# PSU.net
KiCad netlist of a schematic drawn in Altium Designer
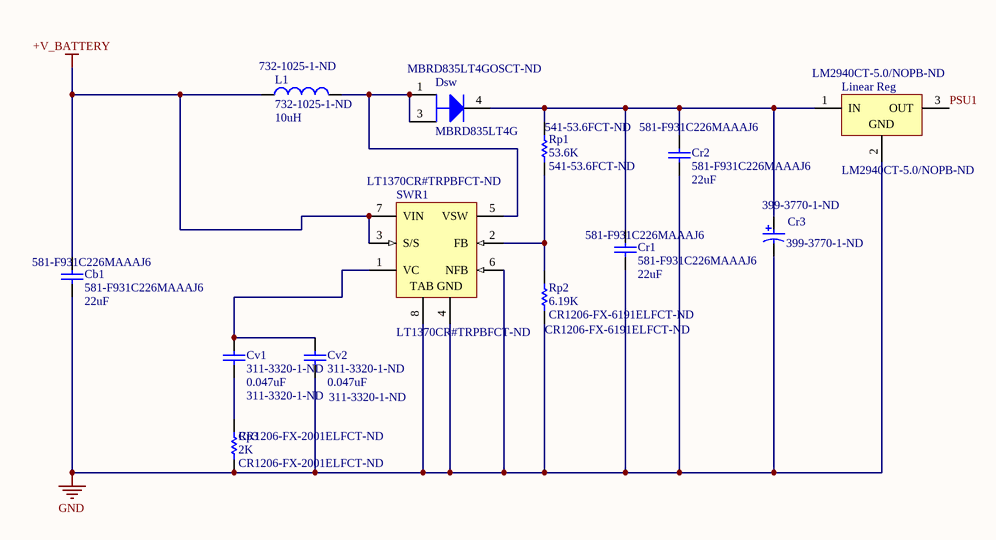
[diagram p0: PSU.SchDoc]

(export (version "E")
  (design (tool "Eeschema 10.0.6"))
  (components
    (comp (ref "Cb1")
      (value "581-F931C226MAAAJ6")
      (footprint "C1206")
      (fields
        (field (name "ALTIUM_VALUE") "22uF")
        (field (name "SUPPLIER PART NUMBER 1") "581-F931C226MAAAJ6")
        (field (name "MANUFACTURER") "Kyocera AVX")
        (field (name "MANUFACTURER PART NUMBER") "F931C226MAAAJ6")
        (field (name "PUBLISHER") "Altium Limited")
      )
      (libsource (lib "Miscellaneous Devices") (part "Cap"))
    )
    (comp (ref "Cr1")
      (value "581-F931C226MAAAJ6")
      (footprint "C1206")
      (fields
        (field (name "ALTIUM_VALUE") "22uF")
        (field (name "SUPPLIER PART NUMBER 1") "581-F931C226MAAAJ6")
        (field (name "MANUFACTURER") "Kyocera AVX")
        (field (name "MANUFACTURER PART NUMBER") "F931C226MAAAJ6")
        (field (name "PUBLISHER") "Altium Limited")
      )
      (libsource (lib "Miscellaneous Devices") (part "Cap"))
    )
    (comp (ref "Cr2")
      (value "581-F931C226MAAAJ6")
      (footprint "C1206")
      (fields
        (field (name "ALTIUM_VALUE") "22uF")
        (field (name "SUPPLIER PART NUMBER 1") "581-F931C226MAAAJ6")
        (field (name "MANUFACTURER") "Kyocera AVX")
        (field (name "MANUFACTURER PART NUMBER") "F931C226MAAAJ6")
        (field (name "PUBLISHER") "Altium Limited")
      )
      (libsource (lib "Miscellaneous Devices") (part "Cap"))
    )
    (comp (ref "Cr3")
      (value "399-3770-1-ND")
      (footprint "KEMT-T491-D_L")
      (fields
        (field (name "MANUFACTURER") "Kemet")
        (field (name "VOLTAGE") "16V")
        (field (name "TOLERANCE") "10%")
        (field (name "SUPPLIER PART NUMBER 1") "399-3770-1-ND")
      )
      (libsource (lib "Altium Content Vault") (part "CAP-P-2"))
    )
    (comp (ref "Cv1")
      (value "311-3320-1-ND")
      (footprint "C1206")
      (description "CAP CER 0.47UF 4V X5R 0201, Digi-key")
      (fields
        (field (name "ALTIUM_VALUE") "0.047uF")
        (field (name "SUPPLIER PART NUMBER 1") "311-3320-1-ND")
        (field (name "MANUFACTURER") "Yageo")
        (field (name "MANUFACTURER PART NUMBER") "CC0201MRX5R4BB474")
        (field (name "PUBLISHER") "Altium Limited")
      )
      (libsource (lib "Miscellaneous Devices") (part "Cap"))
    )
    (comp (ref "Cv2")
      (value "311-3320-1-ND")
      (footprint "C1206")
      (description "CAP CER 0.47UF 4V X5R 0201, Digi-key")
      (fields
        (field (name "ALTIUM_VALUE") "0.047uF")
        (field (name "SUPPLIER PART NUMBER 1") "311-3320-1-ND")
        (field (name "MANUFACTURER") "Yageo")
        (field (name "MANUFACTURER PART NUMBER") "CC0201MRX5R4BB474")
        (field (name "PUBLISHER") "Altium Limited")
      )
      (libsource (lib "Miscellaneous Devices") (part "Cap"))
    )
    (comp (ref "Dsw")
      (value "MBRD835LT4G")
      (footprint "ONSC-DPAK-3-369C-01_V")
      (description "SWITCHMODE(TM) Power Rectifier, 3-Pin DPAK, Pb-Free, Tape and Reel, Digi-key")
      (fields
        (field (name "MANUFACTURER") "On Semiconductor")
        (field (name "SUPPLIER PART NUMBER 1") "MBRD835LT4GOSCT-ND")
      )
      (libsource (lib "Altium Content Vault") (part "ONSC-D-A1A3K4-3_A"))
    )
    (comp (ref "L1")
      (value "732-1025-1-ND")
      (footprint "2029")
      (description "Inductor, SMD 10 uH 1.3 A ±30%, 744042100, Würth Elektronik, Digi-key")
      (fields
        (field (name "ALTIUM_VALUE") "10uH")
        (field (name "SUPPLIER PART NUMBER 1") "732-1025-1-ND")
        (field (name "MANUFACTURER") "Wurth Electronics")
        (field (name "MANUFACTURER PART NUMBER") "744042100")
        (field (name "PUBLISHER") "Altium Limited")
      )
      (libsource (lib "Miscellaneous Devices") (part "Inductor"))
    )
    (comp (ref "Linear Reg")
      (value "LM2940CT-5.0/NOPB-ND")
      (footprint "NDE0003A")
      (description "1A Low Dropout Regulator, 3-pin TO-220, Pb-Free, Digi-key")
      (fields
        (field (name "MANUFACTURER") "Texas Instruments")
        (field (name "SUPPLIER PART NUMBER 1") "LM2940CT-5.0/NOPB-ND")
      )
      (libsource (lib "Altium Content Vault") (part "PM-REG-LM2940-SIL3"))
    )
    (comp (ref "Rp1")
      (value "541-53.6FCT-ND")
      (footprint "C1206")
      (description "Res Thick Film 1206 53.6 Ohm 1% 0.25W(1/4W) ±100ppm/C Molded SMD Automotive Paper T/R, Digi-key")
      (fields
        (field (name "ALTIUM_VALUE") "53.6K")
        (field (name "SUPPLIER PART NUMBER 1") "541-53.6FCT-ND")
        (field (name "MANUFACTURER") "Vishay")
        (field (name "MANUFACTURER PART NUMBER") "CRCW120653R6FKEA")
        (field (name "PUBLISHER") "Altium Limited")
      )
      (libsource (lib "Miscellaneous Devices") (part "Res1"))
    )
    (comp (ref "Rp2")
      (value "CR1206-FX-6191ELFCT-ND")
      (footprint "C1206")
      (description "Thick Film Resistors 6.19K 1%,Digi-key")
      (fields
        (field (name "ALTIUM_VALUE") "6.19K")
        (field (name "SUPPLIER PART NUMBER 1") "CR1206-FX-6191ELFCT-ND")
        (field (name "MANUFACTURER") "Bourns")
        (field (name "MANUFACTURER PART NUMBER") "CR1206-FX-6191ELF")
        (field (name "PUBLISHER") "Altium Limited")
      )
      (libsource (lib "Miscellaneous Devices") (part "Res1"))
    )
    (comp (ref "Rp3")
      (value "CR1206-FX-2001ELFCT-ND")
      (footprint "C1206")
      (description "BOURNS - CR1206-FX-2001ELF - RES, 2K, 1%, 0.25W, 1206, THICK FILM, Digi-key")
      (fields
        (field (name "ALTIUM_VALUE") "2K")
        (field (name "SUPPLIER PART NUMBER 1") "CR1206-FX-2001ELFCT-ND")
        (field (name "MANUFACTURER") "Bourns")
        (field (name "MANUFACTURER PART NUMBER") "CR1206-FX-2001ELF")
        (field (name "PUBLISHER") "Altium Limited")
      )
      (libsource (lib "Miscellaneous Devices") (part "Res1"))
    )
    (comp (ref "SWR1")
      (value "LT1370CR#TRPBFCT-ND")
      (footprint "LT-R-7_L")
      (description "500 kHz High Efficiency 6 A Switching Regulator, 7-pin DPAK (R-7), 0 to 125 degC, Digi-key")
      (fields
        (field (name "MANUFACTURER") "Linear Technology")
        (field (name "PARTNUMBER") "LT1370CR")
        (field (name "SUPPLIER PART NUMBER 1") "LT1370CR#TRPBFCT-ND")
      )
      (libsource (lib "Altium Content Vault") (part "LT-LT1370X-R-7"))
    )
  )
  (nets
    (net (code "1") (name "+V_BATTERY") (class "Default")
      (node (ref "Cb1") (pin "2") (pinfunction "2_2") (pintype "passive"))
      (node (ref "L1") (pin "1") (pinfunction "1_1") (pintype "passive"))
      (node (ref "SWR1") (pin "3") (pinfunction "S/S_3") (pintype "input"))
      (node (ref "SWR1") (pin "7") (pinfunction "VIN_7") (pintype "power_in"))
    )
    (net (code "2") (name "/PSU1") (class "Default")
      (node (ref "Linear Reg") (pin "3") (pinfunction "OUT_3") (pintype "power_in"))
    )
    (net (code "3") (name "GND") (class "Default")
      (node (ref "Cb1") (pin "1") (pinfunction "1_1") (pintype "passive"))
      (node (ref "Cr1") (pin "1") (pinfunction "1_1") (pintype "passive"))
      (node (ref "Cr2") (pin "1") (pinfunction "1_1") (pintype "passive"))
      (node (ref "Cr3") (pin "2") (pinfunction "2_2") (pintype "passive"))
      (node (ref "Cv2") (pin "2") (pinfunction "2_2") (pintype "passive"))
      (node (ref "Linear Reg") (pin "2") (pinfunction "GND_2") (pintype "power_in"))
      (node (ref "Rp2") (pin "1") (pinfunction "1_1") (pintype "passive"))
      (node (ref "Rp3") (pin "1") (pinfunction "1_1") (pintype "passive"))
      (node (ref "SWR1") (pin "4") (pinfunction "GND_4") (pintype "power_in"))
      (node (ref "SWR1") (pin "6") (pinfunction "NFB_6") (pintype "input"))
      (node (ref "SWR1") (pin "8") (pinfunction "TAB_8") (pintype "power_in"))
    )
    (net (code "4") (name "Net-(Cv1-Pad2)") (class "Default")
      (node (ref "Cv1") (pin "2") (pinfunction "2_2") (pintype "passive"))
      (node (ref "Rp3") (pin "2") (pinfunction "2_2") (pintype "passive"))
    )
    (net (code "5") (name "Net-(Dsw-K)") (class "Default")
      (node (ref "Cr1") (pin "2") (pinfunction "2_2") (pintype "passive"))
      (node (ref "Cr2") (pin "2") (pinfunction "2_2") (pintype "passive"))
      (node (ref "Cr3") (pin "1") (pinfunction "1_1") (pintype "passive"))
      (node (ref "Dsw") (pin "4") (pinfunction "K_4") (pintype "passive"))
      (node (ref "Linear Reg") (pin "1") (pinfunction "IN_1") (pintype "power_in"))
      (node (ref "Rp1") (pin "2") (pinfunction "2_2") (pintype "passive"))
    )
    (net (code "6") (name "Net-(SWR1-FB)") (class "Default")
      (node (ref "Rp1") (pin "1") (pinfunction "1_1") (pintype "passive"))
      (node (ref "Rp2") (pin "2") (pinfunction "2_2") (pintype "passive"))
      (node (ref "SWR1") (pin "2") (pinfunction "FB_2") (pintype "input"))
    )
    (net (code "7") (name "Net-(SWR1-VC)") (class "Default")
      (node (ref "Cv1") (pin "1") (pinfunction "1_1") (pintype "passive"))
      (node (ref "Cv2") (pin "1") (pinfunction "1_1") (pintype "passive"))
      (node (ref "SWR1") (pin "1") (pinfunction "VC_1") (pintype "passive"))
    )
    (net (code "8") (name "Net-(SWR1-VSW)") (class "Default")
      (node (ref "Dsw") (pin "1") (pinfunction "A_1") (pintype "passive"))
      (node (ref "Dsw") (pin "3") (pinfunction "A_3") (pintype "passive"))
      (node (ref "L1") (pin "2") (pinfunction "2_2") (pintype "passive"))
      (node (ref "SWR1") (pin "5") (pinfunction "VSW_5") (pintype "power_in"))
    )
  )
)
